# sensore_temp.net
KiCad netlist of a schematic drawn in EAGLE
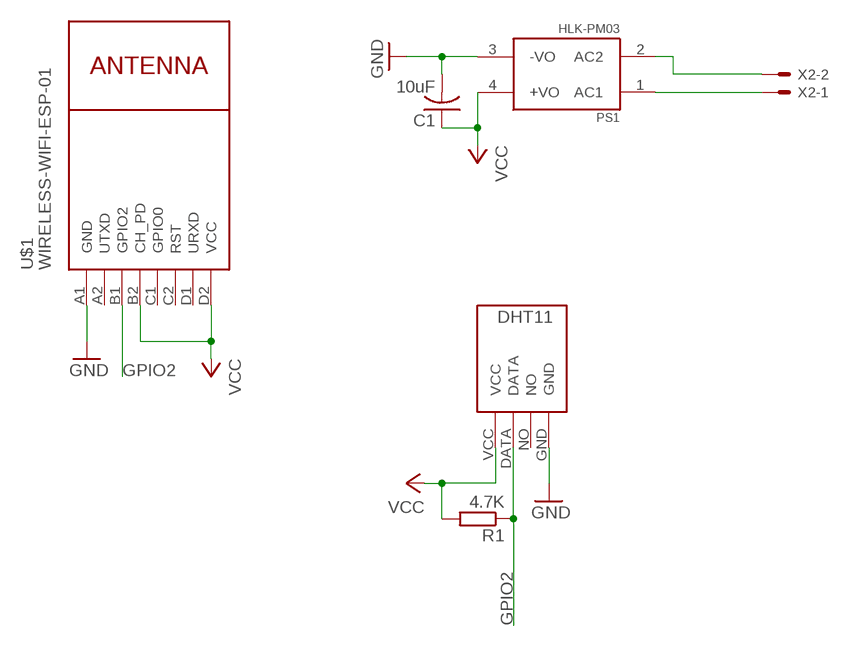
[diagram p0: schematic, sheet 1]

(export (version "E")
  (design (tool "Eeschema 10.0.6"))
  (components
    (comp (ref "C1")
      (value "10uF")
      (footprint "eagle-import:C025-025X050")
      (libsource (lib "eagle-import") (part "C-US025-025X050"))
    )
    (comp (ref "PS1")
      (value "HLK-PM03")
      (footprint "eagle-import:CONV_HLK-PM03")
      (fields (field (name "MF") "Hi-link"))
      (libsource (lib "eagle-import") (part "HLK-PM03"))
    )
    (comp (ref "R1")
      (value "4.7K")
      (footprint "eagle-import:0204_7")
      (libsource (lib "eagle-import") (part "R-EU_0204/7"))
    )
    (comp (ref "U$1")
      (value "WIRELESS-WIFI-ESP-01")
      (footprint "eagle-import:WIRELESS-WIFI-ESP-01")
      (libsource (lib "eagle-import") (part "WIRELESS-WIFI-ESP-01"))
    )
    (comp (ref "U$2")
      (value "DHT11")
      (footprint "eagle-import:DHT11")
      (libsource (lib "eagle-import") (part "DHT11"))
    )
    (comp (ref "X2")
      (value "JST-XH-02-PIN-LONG-PAD")
      (footprint "eagle-import:JST-XH-02-PACKAGE-LONG-PAD")
      (libsource (lib "eagle-import") (part "JST-XH-02-PIN-LONG-PAD"))
    )
  )
  (nets
    (net (code "1") (name "/GPIO2") (class "Default")
      (node (ref "R1") (pin "1") (pinfunction "1_1") (pintype "passive"))
      (node (ref "U$1") (pin "B1") (pinfunction "GPIO2_B1") (pintype "bidirectional"))
      (node (ref "U$2") (pin "DATA") (pinfunction "DATA_DATA") (pintype "bidirectional"))
    )
    (net (code "2") (name "GND") (class "Default")
      (node (ref "C1") (pin "2") (pinfunction "2_2") (pintype "passive"))
      (node (ref "PS1") (pin "3") (pinfunction "-VO_3") (pintype "output"))
      (node (ref "U$1") (pin "A1") (pinfunction "GND_A1") (pintype "power_in"))
      (node (ref "U$2") (pin "GND") (pinfunction "GND_GND") (pintype "bidirectional"))
    )
    (net (code "3") (name "Net-(PS1-AC1)") (class "Default")
      (node (ref "PS1") (pin "1") (pinfunction "AC1_1") (pintype "input"))
      (node (ref "X2") (pin "1") (pinfunction "S_1") (pintype "passive"))
    )
    (net (code "4") (name "Net-(PS1-AC2)") (class "Default")
      (node (ref "PS1") (pin "2") (pinfunction "AC2_2") (pintype "input"))
      (node (ref "X2") (pin "2") (pinfunction "S_2") (pintype "passive"))
    )
    (net (code "5") (name "VCC") (class "Default")
      (node (ref "C1") (pin "1") (pinfunction "1_1") (pintype "passive"))
      (node (ref "PS1") (pin "4") (pinfunction "+VO_4") (pintype "output"))
      (node (ref "R1") (pin "2") (pinfunction "2_2") (pintype "passive"))
      (node (ref "U$1") (pin "B2") (pinfunction "CH_PD_B2") (pintype "bidirectional"))
      (node (ref "U$1") (pin "D2") (pinfunction "VCC_D2") (pintype "power_in"))
      (node (ref "U$2") (pin "VCC") (pinfunction "VCC_VCC") (pintype "bidirectional"))
    )
    (net (code "6") (name "unconnected-(U$1-GPIO0-PadC1)") (class "Default")
      (node (ref "U$1") (pin "C1") (pinfunction "GPIO0_C1") (pintype "bidirectional"))
    )
    (net (code "7") (name "unconnected-(U$1-RST-PadC2)") (class "Default")
      (node (ref "U$1") (pin "C2") (pinfunction "RST_C2") (pintype "bidirectional"))
    )
    (net (code "8") (name "unconnected-(U$1-URXD-PadD1)") (class "Default")
      (node (ref "U$1") (pin "D1") (pinfunction "URXD_D1") (pintype "bidirectional"))
    )
    (net (code "9") (name "unconnected-(U$1-UTXD-PadA2)") (class "Default")
      (node (ref "U$1") (pin "A2") (pinfunction "UTXD_A2") (pintype "bidirectional"))
    )
    (net (code "10") (name "unconnected-(U$2-PadNO)") (class "Default")
      (node (ref "U$2") (pin "NO") (pinfunction "NO_NO") (pintype "bidirectional"))
    )
  )
)
